# MCP3208BOB.net
KiCad netlist of a schematic drawn in EAGLE
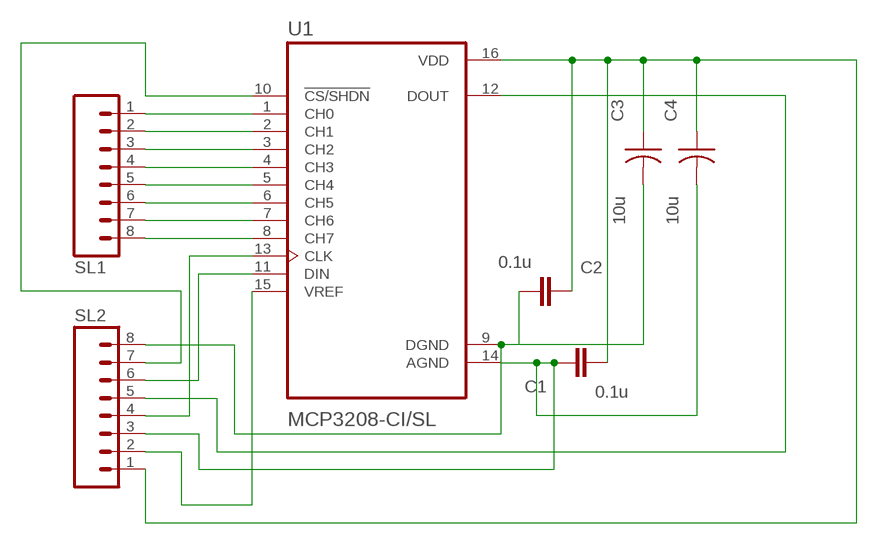
[diagram p0: schematic, sheet 1]

(export (version "E")
  (design (tool "Eeschema 10.0.6"))
  (components
    (comp (ref "C1")
      (value "0.1u")
      (footprint "eagle-import:CAP_0805")
      (fields
        (field (name "DIGIKEY_PART_NUMBER") "311-1140-2-ND")
        (field (name "MANUFACTURER") "Yageo")
        (field (name "MPN") "CC0805KRX7R9BB104")
        (field (name "CREATED_BY") "PCBLayout.com")
      )
      (libsource (lib "eagle-import") (part "CC0805KRX7R9BB104"))
    )
    (comp (ref "C2")
      (value "0.1u")
      (footprint "eagle-import:CAP_0805")
      (fields
        (field (name "DIGIKEY_PART_NUMBER") "311-1140-2-ND")
        (field (name "MANUFACTURER") "Yageo")
        (field (name "MPN") "CC0805KRX7R9BB104")
        (field (name "CREATED_BY") "PCBLayout.com")
      )
      (libsource (lib "eagle-import") (part "CC0805KRX7R9BB104"))
    )
    (comp (ref "C3")
      (value "10u")
      (footprint "eagle-import:CAP_TANT_B")
      (fields
        (field (name "DIGIKEY_PART_NUMBER") "478-1673-2-ND")
        (field (name "MANUFACTURER") "AVX Corporation")
        (field (name "MPN") "TAJB106K016RNJ")
        (field (name "CREATED_BY") "PCBLayout.com")
      )
      (libsource (lib "eagle-import") (part "TAJB106K016RNJ"))
    )
    (comp (ref "C4")
      (value "10u")
      (footprint "eagle-import:CAP_TANT_B")
      (fields
        (field (name "DIGIKEY_PART_NUMBER") "478-1673-2-ND")
        (field (name "MANUFACTURER") "AVX Corporation")
        (field (name "MPN") "TAJB106K016RNJ")
        (field (name "CREATED_BY") "PCBLayout.com")
      )
      (libsource (lib "eagle-import") (part "TAJB106K016RNJ"))
    )
    (comp (ref "SL1")
      (value "M08")
      (footprint "eagle-import:08P")
      (libsource (lib "eagle-import") (part "M08"))
    )
    (comp (ref "SL2")
      (value "M08")
      (footprint "eagle-import:08P")
      (libsource (lib "eagle-import") (part "M08"))
    )
    (comp (ref "U1")
      (value "MCP3208-CI/SL")
      (footprint "eagle-import:SOIC127P600X175-16N")
      (fields (field (name "MF") "Microchip"))
      (libsource (lib "eagle-import") (part "MCP3208-CI/SL"))
    )
  )
  (nets
    (net (code "1") (name "Net-(U1-AGND)") (class "Default")
      (node (ref "C1") (pin "1") (pinfunction "1_1") (pintype "passive"))
      (node (ref "C4") (pin "2") (pinfunction "2_2") (pintype "passive"))
      (node (ref "SL2") (pin "3") (pinfunction "3_3") (pintype "passive"))
      (node (ref "U1") (pin "14") (pinfunction "AGND_14") (pintype "power_in"))
    )
    (net (code "2") (name "Net-(U1-CH0)") (class "Default")
      (node (ref "SL1") (pin "1") (pinfunction "1_1") (pintype "passive"))
      (node (ref "U1") (pin "1") (pinfunction "CH0_1") (pintype "input"))
    )
    (net (code "3") (name "Net-(U1-CH1)") (class "Default")
      (node (ref "SL1") (pin "2") (pinfunction "2_2") (pintype "passive"))
      (node (ref "U1") (pin "2") (pinfunction "CH1_2") (pintype "input"))
    )
    (net (code "4") (name "Net-(U1-CH2)") (class "Default")
      (node (ref "SL1") (pin "3") (pinfunction "3_3") (pintype "passive"))
      (node (ref "U1") (pin "3") (pinfunction "CH2_3") (pintype "input"))
    )
    (net (code "5") (name "Net-(U1-CH3)") (class "Default")
      (node (ref "SL1") (pin "4") (pinfunction "4_4") (pintype "passive"))
      (node (ref "U1") (pin "4") (pinfunction "CH3_4") (pintype "input"))
    )
    (net (code "6") (name "Net-(U1-CH4)") (class "Default")
      (node (ref "SL1") (pin "5") (pinfunction "5_5") (pintype "passive"))
      (node (ref "U1") (pin "5") (pinfunction "CH4_5") (pintype "input"))
    )
    (net (code "7") (name "Net-(U1-CH5)") (class "Default")
      (node (ref "SL1") (pin "6") (pinfunction "6_6") (pintype "passive"))
      (node (ref "U1") (pin "6") (pinfunction "CH5_6") (pintype "input"))
    )
    (net (code "8") (name "Net-(U1-CH6)") (class "Default")
      (node (ref "SL1") (pin "7") (pinfunction "7_7") (pintype "passive"))
      (node (ref "U1") (pin "7") (pinfunction "CH6_7") (pintype "input"))
    )
    (net (code "9") (name "Net-(U1-CH7)") (class "Default")
      (node (ref "SL1") (pin "8") (pinfunction "8_8") (pintype "passive"))
      (node (ref "U1") (pin "8") (pinfunction "CH7_8") (pintype "input"))
    )
    (net (code "10") (name "Net-(U1-CLK)") (class "Default")
      (node (ref "SL2") (pin "4") (pinfunction "4_4") (pintype "passive"))
      (node (ref "U1") (pin "13") (pinfunction "CLK_13") (pintype "input"))
    )
    (net (code "11") (name "Net-(U1-DGND)") (class "Default")
      (node (ref "C2") (pin "2") (pinfunction "2_2") (pintype "passive"))
      (node (ref "C3") (pin "2") (pinfunction "2_2") (pintype "passive"))
      (node (ref "SL2") (pin "8") (pinfunction "8_8") (pintype "passive"))
      (node (ref "U1") (pin "9") (pinfunction "DGND_9") (pintype "power_in"))
    )
    (net (code "12") (name "Net-(U1-DIN)") (class "Default")
      (node (ref "SL2") (pin "6") (pinfunction "6_6") (pintype "passive"))
      (node (ref "U1") (pin "11") (pinfunction "DIN_11") (pintype "input"))
    )
    (net (code "13") (name "Net-(U1-DOUT)") (class "Default")
      (node (ref "SL2") (pin "5") (pinfunction "5_5") (pintype "passive"))
      (node (ref "U1") (pin "12") (pinfunction "DOUT_12") (pintype "output"))
    )
    (net (code "14") (name "Net-(U1-VDD)") (class "Default")
      (node (ref "C1") (pin "2") (pinfunction "2_2") (pintype "passive"))
      (node (ref "C2") (pin "1") (pinfunction "1_1") (pintype "passive"))
      (node (ref "C3") (pin "1") (pinfunction "1_1") (pintype "passive"))
      (node (ref "C4") (pin "1") (pinfunction "1_1") (pintype "passive"))
      (node (ref "SL2") (pin "1") (pinfunction "1_1") (pintype "passive"))
      (node (ref "U1") (pin "16") (pinfunction "VDD_16") (pintype "power_in"))
    )
    (net (code "15") (name "Net-(U1-VREF)") (class "Default")
      (node (ref "SL2") (pin "2") (pinfunction "2_2") (pintype "passive"))
      (node (ref "U1") (pin "15") (pinfunction "VREF_15") (pintype "input"))
    )
    (net (code "16") (name "Net-(U1-~{CS{slash}SHDN})") (class "Default")
      (node (ref "SL2") (pin "7") (pinfunction "7_7") (pintype "passive"))
      (node (ref "U1") (pin "10") (pinfunction "~{CS/SHDN}_10") (pintype "input"))
    )
  )
)
